# Power.net
KiCad netlist of a schematic drawn in Altium Designer
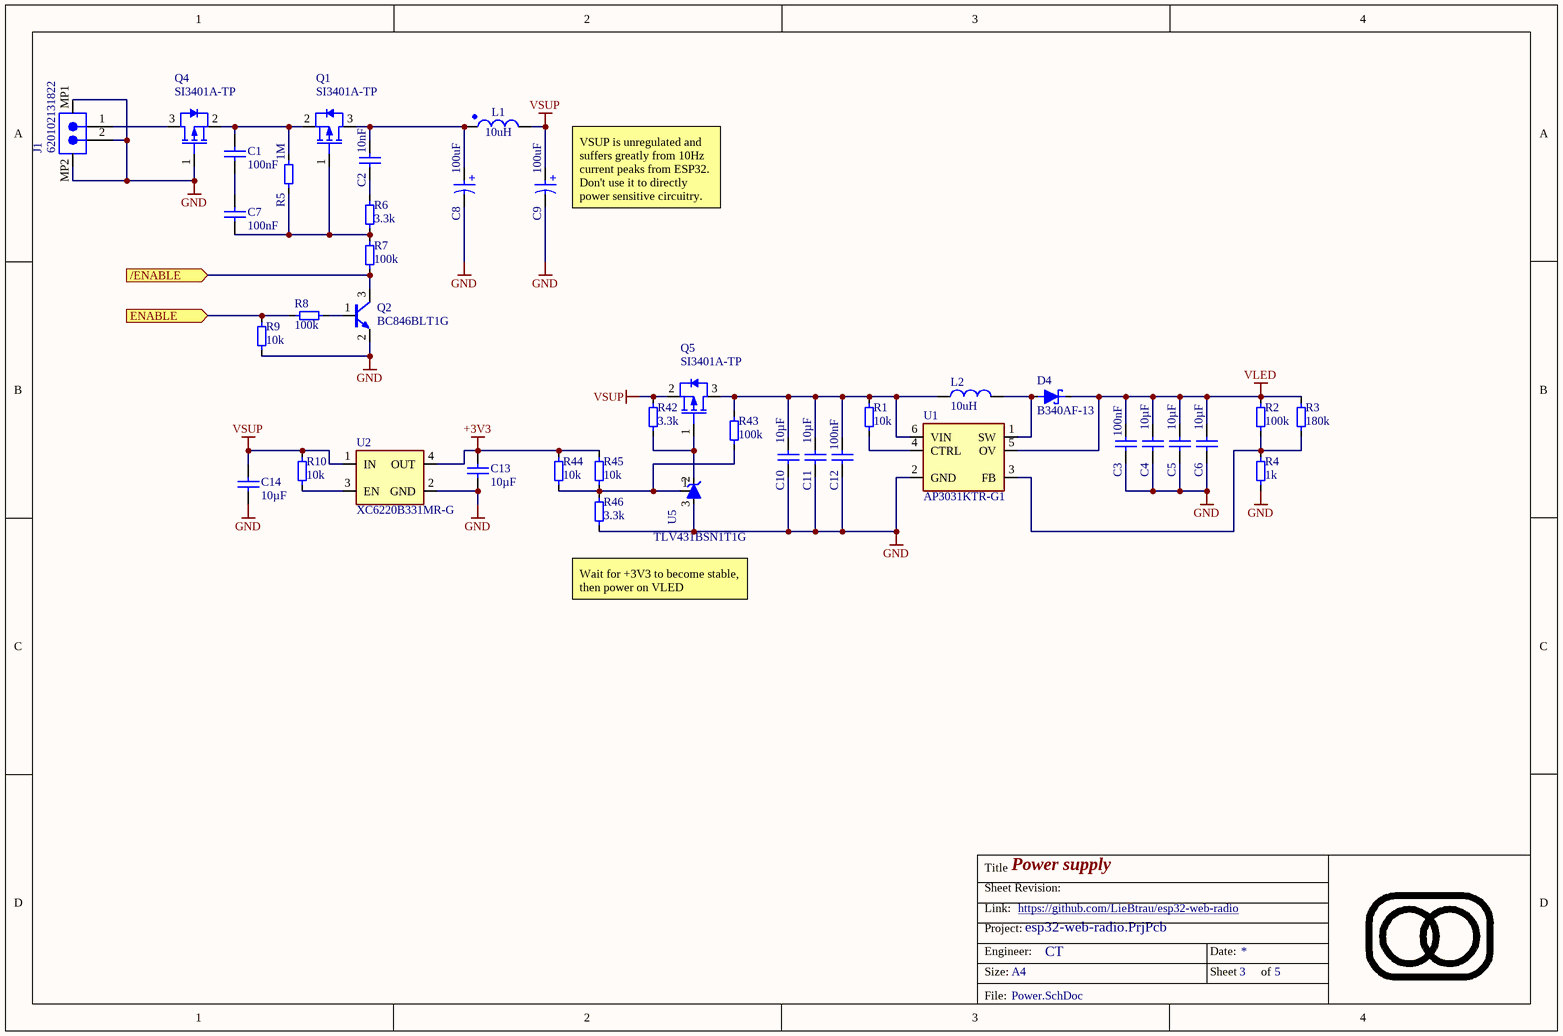
[diagram p0: Power.SchDoc]

(export (version "E")
  (design (tool "Eeschema 10.0.6"))
  (components
    (comp (ref "C1")
      (value "100nF")
      (footprint "0603-C-N")
      (description "WCAP-CSGP Multilayer Ceramic Chip Capacitor, General Purpose, size 0603, X7R, 100nF, 50VDC")
      (fields (field (name "TOLERANCE") "10%") (field (name "JLCPCB PART #") "C14663"))
      (libsource (lib "7c7 Engineering") (part "CAP-NP-2"))
    )
    (comp (ref "C2")
      (value "10nF")
      (footprint "0603-C-N")
      (description "Capacitor MLCC, General Purpose, size 0603, X7R, 10nF, +/-10%, 50V")
      (fields (field (name "TOLERANCE") "10%") (field (name "JLCPCB PART #") "C57112"))
      (libsource (lib "7c7 Engineering") (part "CAP-NP-2"))
    )
    (comp (ref "C3")
      (value "100nF")
      (footprint "0603-C-N")
      (description "WCAP-CSGP Multilayer Ceramic Chip Capacitor, General Purpose, size 0603, X7R, 100nF, 50VDC")
      (fields (field (name "TOLERANCE") "10%") (field (name "JLCPCB PART #") "C14663"))
      (libsource (lib "7c7 Engineering") (part "CAP-NP-2"))
    )
    (comp (ref "C4")
      (value "10µF")
      (footprint "WCAP-CSGP_1210_L3.2W2.5H2.5")
      (description "WCAP-CSGP Multilayer Ceramic Chip Capacitor, General Purpose, size 1210, X7R, 10µF, 50VDC")
      (fields (field (name "JLCPCB PART #") "C2918502") (field (name "TOLERANCE") "10%"))
      (libsource (lib "7c7 Engineering") (part "CAP-NP-2"))
    )
    (comp (ref "C5")
      (value "10µF")
      (footprint "WCAP-CSGP_1210_L3.2W2.5H2.5")
      (description "WCAP-CSGP Multilayer Ceramic Chip Capacitor, General Purpose, size 1210, X7R, 10µF, 50VDC")
      (fields (field (name "JLCPCB PART #") "C2918502") (field (name "TOLERANCE") "10%"))
      (libsource (lib "7c7 Engineering") (part "CAP-NP-2"))
    )
    (comp (ref "C6")
      (value "10µF")
      (footprint "WCAP-CSGP_1210_L3.2W2.5H2.5")
      (description "WCAP-CSGP Multilayer Ceramic Chip Capacitor, General Purpose, size 1210, X7R, 10µF, 50VDC")
      (fields (field (name "JLCPCB PART #") "C2918502") (field (name "TOLERANCE") "10%"))
      (libsource (lib "7c7 Engineering") (part "CAP-NP-2"))
    )
    (comp (ref "C7")
      (value "100nF")
      (footprint "0603-C-N")
      (description "WCAP-CSGP Multilayer Ceramic Chip Capacitor, General Purpose, size 0603, X7R, 100nF, 50VDC")
      (fields (field (name "TOLERANCE") "10%") (field (name "JLCPCB PART #") "C14663"))
      (libsource (lib "7c7 Engineering") (part "CAP-NP-2"))
    )
    (comp (ref "C8")
      (value "865080343009")
      (footprint "WCAP-ASLI_D6.3H5.5")
      (description "WCAP-ASLI Aluminum Electrolytic Capacitor, V-Chip, D6.3 x H5.5mm, 100uF, 16V")
      (fields
        (field (name "CAPACITANCE") "100uF")
        (field (name "MANUFACTURER") "Wurth Elektronik")
        (field (name "JLCPCB PART #") "C111600")
      )
      (libsource (lib "7c7 Engineering") (part "865081763011"))
    )
    (comp (ref "C9")
      (value "865080343009")
      (footprint "WCAP-ASLI_D6.3H5.5")
      (description "WCAP-ASLI Aluminum Electrolytic Capacitor, V-Chip, D6.3 x H5.5mm, 100uF, 16V")
      (fields
        (field (name "CAPACITANCE") "100uF")
        (field (name "MANUFACTURER") "Wurth Elektronik")
        (field (name "JLCPCB PART #") "C111600")
      )
      (libsource (lib "7c7 Engineering") (part "865081763011"))
    )
    (comp (ref "C10")
      (value "10µF")
      (footprint "1206-C-N")
      (description "WCAP-CSGP Multilayer Ceramic Chip Capacitor, General Purpose, size 1206, X7R, 10µF, 10VDC")
      (fields (field (name "TOLERANCE") "10%") (field (name "JLCPCB PART #") "C97953"))
      (libsource (lib "7c7 Engineering") (part "CAP-NP-2"))
    )
    (comp (ref "C11")
      (value "10µF")
      (footprint "1206-C-N")
      (description "WCAP-CSGP Multilayer Ceramic Chip Capacitor, General Purpose, size 1206, X7R, 10µF, 10VDC")
      (fields (field (name "TOLERANCE") "10%") (field (name "JLCPCB PART #") "C97953"))
      (libsource (lib "7c7 Engineering") (part "CAP-NP-2"))
    )
    (comp (ref "C12")
      (value "100nF")
      (footprint "0603-C-N")
      (description "WCAP-CSGP Multilayer Ceramic Chip Capacitor, General Purpose, size 0603, X7R, 100nF, 50VDC")
      (fields (field (name "TOLERANCE") "10%") (field (name "JLCPCB PART #") "C14663"))
      (libsource (lib "7c7 Engineering") (part "CAP-NP-2"))
    )
    (comp (ref "C13")
      (value "10µF")
      (footprint "1206-C-N")
      (description "WCAP-CSGP Multilayer Ceramic Chip Capacitor, General Purpose, size 1206, X7R, 10µF, 10VDC")
      (fields (field (name "TOLERANCE") "10%") (field (name "JLCPCB PART #") "C97953"))
      (libsource (lib "7c7 Engineering") (part "CAP-NP-2"))
    )
    (comp (ref "C14")
      (value "10µF")
      (footprint "1206-C-N")
      (description "WCAP-CSGP Multilayer Ceramic Chip Capacitor, General Purpose, size 1206, X7R, 10µF, 10VDC")
      (fields (field (name "TOLERANCE") "10%") (field (name "JLCPCB PART #") "C97953"))
      (libsource (lib "7c7 Engineering") (part "CAP-NP-2"))
    )
    (comp (ref "D4")
      (value "B340AF-13")
      (footprint "DO-214AC_UNI")
      (description "Diode 40 V 3A Surface Mount SMAF")
      (fields (field (name "JLCPCB PART #") "C5310924"))
      (libsource (lib "7c7 Engineering") (part "DIODE-SKY-2"))
    )
    (comp (ref "J1")
      (value "620102131822")
      (footprint "620102131822")
      (description "WR-WTB SMT Male Horizontal Shrouded Header, pitch 2mm, 2p")
      (fields (field (name "JLCPCB PART #") "C295747") (field (name "PUBLISHER") "Wurth Elektronik"))
      (libsource (lib "7c7 Engineering") (part "HDR_2P_2MP"))
    )
    (comp (ref "L1")
      (value "78438357100")
      (footprint "WE-MAIA_4030")
      (description "WE-MAIA SMT Power Inductor, size 4030, 10uH, 3.05A, 110mOhm")
      (fields
        (field (name "JLCPCB PART #") "C167879")
        (field (name "INDUCTANCE") "10uH")
        (field (name "MANUFACTURER") "Wurth Elektronik")
      )
      (libsource (lib "7c7 Engineering") (part "IND_POLAR-2"))
    )
    (comp (ref "L2")
      (value "10uH")
      (footprint "WE-PMI_1008_L2.5W2H1.2")
      (description "Inductor Power Chip Shielded Wirewound 10uH 20% 1MHz Metal 0.95A 0.48Ohm DCR 1008 T/R")
      (fields (field (name "TOLERANCE") "20%") (field (name "JLCPCB PART #") "C2042388"))
      (libsource (lib "7c7 Engineering") (part "IND"))
    )
    (comp (ref "Q1")
      (value "SI3401A-TP")
      (footprint "SOT-23-3-N")
      (description "Trans Mosfet P-ch 30V 4.2A 3-PIN SOT-23 T/r")
      (fields (field (name "JLCPCB PART #") "C15127"))
      (libsource (lib "7c7 Engineering") (part "PEMOS-GSD-3"))
    )
    (comp (ref "Q2")
      (value "BC846BLT1G")
      (footprint "SOT-23-3-N")
      (description "NPN Ic=100mA Vceo=65V hfe=200~450 P=225mW SOT-23")
      (fields (field (name "JLCPCB PART #") "C82477"))
      (libsource (lib "7c7 Engineering") (part "BJT-NPN-BEC"))
    )
    (comp (ref "Q4")
      (value "SI3401A-TP")
      (footprint "SOT-23-3-N")
      (description "Trans Mosfet P-ch 30V 4.2A 3-PIN SOT-23 T/r")
      (fields (field (name "JLCPCB PART #") "C15127"))
      (libsource (lib "7c7 Engineering") (part "PEMOS-GSD-3"))
    )
    (comp (ref "Q5")
      (value "SI3401A-TP")
      (footprint "SOT-23-3-N")
      (description "Trans Mosfet P-ch 30V 4.2A 3-PIN SOT-23 T/r")
      (fields (field (name "JLCPCB PART #") "C15127"))
      (libsource (lib "7c7 Engineering") (part "PEMOS-GSD-3"))
    )
    (comp (ref "R1")
      (value "10k")
      (footprint "0603-R-N")
      (description "Chip Resistor, Thick Film, General Purpose, 0603, 100mW, 50V, 10 kOhm, +/-1%")
      (fields (field (name "JLCPCB PART #") "C25804") (field (name "TOLERANCE") "1%"))
      (libsource (lib "") (part "RES_2"))
    )
    (comp (ref "R2")
      (value "100k")
      (footprint "0603-R-N")
      (description "Chip Resistor, Thick Film, General Purpose, 0603, 100mW, 50V, 100 kOhm, +/-1%")
      (fields (field (name "TOLERANCE") "1%") (field (name "JLCPCB PART #") "C25803"))
      (libsource (lib "") (part "RES_1"))
    )
    (comp (ref "R3")
      (value "180k")
      (footprint "0603-R-N")
      (description "Res Thick Film 0603 180K Ohm 1% 0.1W(1/10W) ±100ppm/C Pad SMD T/R")
      (fields (field (name "TOLERANCE") "1%") (field (name "JLCPCB PART #") "C22827"))
      (libsource (lib "") (part "RES_2"))
    )
    (comp (ref "R4")
      (value "1k")
      (footprint "0603-R-N")
      (description "Chip Resistor, Thick Film, General Purpose, 0603, 100mW, 50V, 1 kOhm, +/-1%")
      (fields (field (name "TOLERANCE") "1%") (field (name "JLCPCB PART #") "C21190"))
      (libsource (lib "") (part "RES_1"))
    )
    (comp (ref "R5")
      (value "1M")
      (footprint "0603-R-N")
      (description "Chip Resistor, Thick Film, General Purpose, 0603, 100mW, 50V, 1 MOhm, +/-1%")
      (fields (field (name "TOLERANCE") "1%") (field (name "JLCPCB PART #") "C22935"))
      (libsource (lib "") (part "RES_2"))
    )
    (comp (ref "R6")
      (value "3.3k")
      (footprint "0603-R-N")
      (description "Chip Resistor, Thick Film, General Purpose, 0603, 100mW, 50V, 3.3 kOhm, +/-1%")
      (fields (field (name "TOLERANCE") "1%") (field (name "JLCPCB PART #") "C22978"))
      (libsource (lib "") (part "RES_1"))
    )
    (comp (ref "R7")
      (value "100k")
      (footprint "0603-R-N")
      (description "Chip Resistor, Thick Film, General Purpose, 0603, 100mW, 50V, 100 kOhm, +/-1%")
      (fields (field (name "TOLERANCE") "1%") (field (name "JLCPCB PART #") "C25803"))
      (libsource (lib "") (part "RES_1"))
    )
    (comp (ref "R8")
      (value "100k")
      (footprint "0603-R-N")
      (description "Chip Resistor, Thick Film, General Purpose, 0603, 100mW, 50V, 100 kOhm, +/-1%")
      (fields (field (name "TOLERANCE") "1%") (field (name "JLCPCB PART #") "C25803"))
      (libsource (lib "") (part "RES_2"))
    )
    (comp (ref "R9")
      (value "10k")
      (footprint "0603-R-N")
      (description "Chip Resistor, Thick Film, General Purpose, 0603, 100mW, 50V, 10 kOhm, +/-1%")
      (fields (field (name "JLCPCB PART #") "C25804") (field (name "TOLERANCE") "1%"))
      (libsource (lib "7c7 Engineering") (part "RES"))
    )
    (comp (ref "R10")
      (value "10k")
      (footprint "0603-R-N")
      (description "Chip Resistor, Thick Film, General Purpose, 0603, 100mW, 50V, 10 kOhm, +/-1%")
      (fields (field (name "JLCPCB PART #") "C25804") (field (name "TOLERANCE") "1%"))
      (libsource (lib "") (part "RES_2"))
    )
    (comp (ref "R42")
      (value "3.3k")
      (footprint "0603-R-N")
      (description "Chip Resistor, Thick Film, General Purpose, 0603, 100mW, 50V, 3.3 kOhm, +/-1%")
      (fields (field (name "TOLERANCE") "1%") (field (name "JLCPCB PART #") "C22978"))
      (libsource (lib "") (part "RES_1"))
    )
    (comp (ref "R43")
      (value "100k")
      (footprint "0603-R-N")
      (description "Chip Resistor, Thick Film, General Purpose, 0603, 100mW, 50V, 100 kOhm, +/-1%")
      (fields (field (name "TOLERANCE") "1%") (field (name "JLCPCB PART #") "C25803"))
      (libsource (lib "7c7 Engineering") (part "RES"))
    )
    (comp (ref "R44")
      (value "10k")
      (footprint "0603-R-N")
      (description "Chip Resistor, Thick Film, General Purpose, 0603, 100mW, 50V, 10 kOhm, +/-1%")
      (fields (field (name "JLCPCB PART #") "C25804") (field (name "TOLERANCE") "1%"))
      (libsource (lib "7c7 Engineering") (part "RES"))
    )
    (comp (ref "R45")
      (value "10k")
      (footprint "0603-R-N")
      (description "Chip Resistor, Thick Film, General Purpose, 0603, 100mW, 50V, 10 kOhm, +/-1%")
      (fields (field (name "JLCPCB PART #") "C25804") (field (name "TOLERANCE") "1%"))
      (libsource (lib "7c7 Engineering") (part "RES"))
    )
    (comp (ref "R46")
      (value "3.3k")
      (footprint "0603-R-N")
      (description "Chip Resistor, Thick Film, General Purpose, 0603, 100mW, 50V, 3.3 kOhm, +/-1%")
      (fields (field (name "TOLERANCE") "1%") (field (name "JLCPCB PART #") "C22978"))
      (libsource (lib "") (part "RES_1"))
    )
    (comp (ref "U1")
      (value "AP3031KTR-G1")
      (footprint "SOT-23-6")
      (description "AP3031 Series 2.7 to 16 Vin 1.4 A White LED Step Up Converter-SOT-23-6")
      (fields (field (name "JLCPCB PART #") "C82636"))
      (libsource (lib "7c7 Engineering") (part "AP3031KTR-G1-Symbol-1"))
    )
    (comp (ref "U2")
      (value "XC6220B331MR-G")
      (footprint "SOT25-N")
      (description "Fixed LDO 3.3V, 1%, 1A, Iq 108uA, -40°C to 85°C")
      (fields (field (name "JLCPCB PART #") "C86534"))
      (libsource (lib "7c7 Engineering") (part "LDO-with-enable"))
    )
    (comp (ref "U5")
      (value "TLV431BSN1T1G")
      (footprint "SOT-23-3-N")
      (description "Adjustable Shunt Voltage Reference 1.24 - 16V; +/-0.5%; 3-Pin SOT-23")
      (fields (field (name "TOLERANCE") "0.5%") (field (name "JLCPCB PART #") "C91075"))
      (libsource (lib "7c7 Engineering") (part "TLV431BSN1T1G"))
    )
  )
  (nets
    (net (code "1") (name "+3V3") (class "Default")
      (node (ref "C13") (pin "2") (pinfunction "2_2") (pintype "passive"))
      (node (ref "R44") (pin "2") (pinfunction "2_2") (pintype "passive"))
      (node (ref "R45") (pin "2") (pinfunction "2_2") (pintype "passive"))
      (node (ref "U2") (pin "4") (pinfunction "OUT_4") (pintype "power_in"))
    )
    (net (code "2") (name "/ENABLE") (class "Default")
      (node (ref "R8") (pin "1") (pinfunction "1_1") (pintype "passive"))
      (node (ref "R9") (pin "2") (pinfunction "2_2") (pintype "passive"))
    )
    (net (code "3") (name "/{slash}ENABLE") (class "Default")
      (node (ref "Q2") (pin "3") (pinfunction "C_3") (pintype "passive"))
      (node (ref "R7") (pin "2") (pinfunction "2_2") (pintype "passive"))
    )
    (net (code "4") (name "GND") (class "Default")
      (node (ref "C10") (pin "1") (pinfunction "1_1") (pintype "passive"))
      (node (ref "C11") (pin "1") (pinfunction "1_1") (pintype "passive"))
      (node (ref "C12") (pin "1") (pinfunction "1_1") (pintype "passive"))
      (node (ref "C13") (pin "1") (pinfunction "1_1") (pintype "passive"))
      (node (ref "C14") (pin "1") (pinfunction "1_1") (pintype "passive"))
      (node (ref "C3") (pin "1") (pinfunction "1_1") (pintype "passive"))
      (node (ref "C4") (pin "1") (pinfunction "1_1") (pintype "passive"))
      (node (ref "C5") (pin "1") (pinfunction "1_1") (pintype "passive"))
      (node (ref "C6") (pin "1") (pinfunction "1_1") (pintype "passive"))
      (node (ref "C8") (pin "2") (pinfunction "N_2") (pintype "passive"))
      (node (ref "C9") (pin "2") (pinfunction "N_2") (pintype "passive"))
      (node (ref "J1") (pin "2") (pinfunction "2_2") (pintype "passive"))
      (node (ref "J1") (pin "MP1") (pinfunction "MP1_MP1") (pintype "passive"))
      (node (ref "J1") (pin "MP2") (pinfunction "MP2_MP2") (pintype "passive"))
      (node (ref "Q2") (pin "2") (pinfunction "E_2") (pintype "passive"))
      (node (ref "Q4") (pin "1") (pinfunction "GATE_1") (pintype "passive"))
      (node (ref "R4") (pin "2") (pinfunction "2_2") (pintype "passive"))
      (node (ref "R46") (pin "2") (pinfunction "2_2") (pintype "passive"))
      (node (ref "R9") (pin "1") (pinfunction "1_1") (pintype "passive"))
      (node (ref "U1") (pin "2") (pinfunction "GND_2") (pintype "power_in"))
      (node (ref "U2") (pin "2") (pinfunction "GND_2") (pintype "power_in"))
      (node (ref "U5") (pin "3") (pinfunction "A_3") (pintype "power_in"))
    )
    (net (code "5") (name "Net-(C1-Pad1)") (class "Default")
      (node (ref "C1") (pin "1") (pinfunction "1_1") (pintype "passive"))
      (node (ref "C7") (pin "1") (pinfunction "1_1") (pintype "passive"))
    )
    (net (code "6") (name "Net-(C2-Pad1)") (class "Default")
      (node (ref "C2") (pin "1") (pinfunction "1_1") (pintype "passive"))
      (node (ref "R6") (pin "1") (pinfunction "1_1") (pintype "passive"))
    )
    (net (code "7") (name "Net-(C8-P)") (class "Default")
      (node (ref "C2") (pin "2") (pinfunction "2_2") (pintype "passive"))
      (node (ref "C8") (pin "1") (pinfunction "P_1") (pintype "passive"))
      (node (ref "L1") (pin "1") (pinfunction "1_1") (pintype "passive"))
      (node (ref "Q1") (pin "3") (pinfunction "DRAIN_3") (pintype "passive"))
    )
    (net (code "8") (name "Net-(D4-A)") (class "Default")
      (node (ref "D4") (pin "2") (pinfunction "A_2") (pintype "passive"))
      (node (ref "L2") (pin "2") (pinfunction "2_2") (pintype "passive"))
      (node (ref "U1") (pin "1") (pinfunction "SW_1") (pintype "power_in"))
    )
    (net (code "9") (name "Net-(Q1-GATE)") (class "Default")
      (node (ref "C7") (pin "2") (pinfunction "2_2") (pintype "passive"))
      (node (ref "Q1") (pin "1") (pinfunction "GATE_1") (pintype "passive"))
      (node (ref "R5") (pin "1") (pinfunction "1_1") (pintype "passive"))
      (node (ref "R6") (pin "2") (pinfunction "2_2") (pintype "passive"))
      (node (ref "R7") (pin "1") (pinfunction "1_1") (pintype "passive"))
    )
    (net (code "10") (name "Net-(Q1-SOURCE)") (class "Default")
      (node (ref "C1") (pin "2") (pinfunction "2_2") (pintype "passive"))
      (node (ref "Q1") (pin "2") (pinfunction "SOURCE_2") (pintype "passive"))
      (node (ref "Q4") (pin "2") (pinfunction "SOURCE_2") (pintype "passive"))
      (node (ref "R5") (pin "2") (pinfunction "2_2") (pintype "passive"))
    )
    (net (code "11") (name "Net-(Q2-B)") (class "Default")
      (node (ref "Q2") (pin "1") (pinfunction "B_1") (pintype "passive"))
      (node (ref "R8") (pin "2") (pinfunction "2_2") (pintype "passive"))
    )
    (net (code "12") (name "Net-(Q4-DRAIN)") (class "Default")
      (node (ref "J1") (pin "1") (pinfunction "1_1") (pintype "passive"))
      (node (ref "Q4") (pin "3") (pinfunction "DRAIN_3") (pintype "passive"))
    )
    (net (code "13") (name "Net-(Q5-DRAIN)") (class "Default")
      (node (ref "C10") (pin "2") (pinfunction "2_2") (pintype "passive"))
      (node (ref "C11") (pin "2") (pinfunction "2_2") (pintype "passive"))
      (node (ref "C12") (pin "2") (pinfunction "2_2") (pintype "passive"))
      (node (ref "L2") (pin "1") (pinfunction "1_1") (pintype "passive"))
      (node (ref "Q5") (pin "3") (pinfunction "DRAIN_3") (pintype "passive"))
      (node (ref "R1") (pin "2") (pinfunction "2_2") (pintype "passive"))
      (node (ref "R43") (pin "2") (pinfunction "2_2") (pintype "passive"))
      (node (ref "U1") (pin "6") (pinfunction "VIN_6") (pintype "power_in"))
    )
    (net (code "14") (name "Net-(Q5-GATE)") (class "Default")
      (node (ref "Q5") (pin "1") (pinfunction "GATE_1") (pintype "passive"))
      (node (ref "R42") (pin "2") (pinfunction "2_2") (pintype "passive"))
      (node (ref "U5") (pin "2") (pinfunction "C_2") (pintype "power_in"))
    )
    (net (code "15") (name "Net-(U1-CTRL)") (class "Default")
      (node (ref "R1") (pin "1") (pinfunction "1_1") (pintype "passive"))
      (node (ref "U1") (pin "4") (pinfunction "CTRL_4") (pintype "power_in"))
    )
    (net (code "16") (name "Net-(U1-FB)") (class "Default")
      (node (ref "R2") (pin "2") (pinfunction "2_2") (pintype "passive"))
      (node (ref "R3") (pin "1") (pinfunction "1_1") (pintype "passive"))
      (node (ref "R4") (pin "1") (pinfunction "1_1") (pintype "passive"))
      (node (ref "U1") (pin "3") (pinfunction "FB_3") (pintype "power_in"))
    )
    (net (code "17") (name "Net-(U2-EN)") (class "Default")
      (node (ref "R10") (pin "1") (pinfunction "1_1") (pintype "passive"))
      (node (ref "U2") (pin "3") (pinfunction "EN_3") (pintype "passive"))
    )
    (net (code "18") (name "Net-(U5-rEF)") (class "Default")
      (node (ref "R43") (pin "1") (pinfunction "1_1") (pintype "passive"))
      (node (ref "R44") (pin "1") (pinfunction "1_1") (pintype "passive"))
      (node (ref "R45") (pin "1") (pinfunction "1_1") (pintype "passive"))
      (node (ref "R46") (pin "1") (pinfunction "1_1") (pintype "passive"))
      (node (ref "U5") (pin "1") (pinfunction "rEF_1") (pintype "passive"))
    )
    (net (code "19") (name "VLED") (class "Default")
      (node (ref "C3") (pin "2") (pinfunction "2_2") (pintype "passive"))
      (node (ref "C4") (pin "2") (pinfunction "2_2") (pintype "passive"))
      (node (ref "C5") (pin "2") (pinfunction "2_2") (pintype "passive"))
      (node (ref "C6") (pin "2") (pinfunction "2_2") (pintype "passive"))
      (node (ref "D4") (pin "1") (pinfunction "K_1") (pintype "passive"))
      (node (ref "R2") (pin "1") (pinfunction "1_1") (pintype "passive"))
      (node (ref "R3") (pin "2") (pinfunction "2_2") (pintype "passive"))
      (node (ref "U1") (pin "5") (pinfunction "OV_5") (pintype "power_in"))
    )
    (net (code "20") (name "VSUP") (class "Default")
      (node (ref "C14") (pin "2") (pinfunction "2_2") (pintype "passive"))
      (node (ref "C9") (pin "1") (pinfunction "P_1") (pintype "passive"))
      (node (ref "L1") (pin "2") (pinfunction "2_2") (pintype "passive"))
      (node (ref "Q5") (pin "2") (pinfunction "SOURCE_2") (pintype "passive"))
      (node (ref "R10") (pin "2") (pinfunction "2_2") (pintype "passive"))
      (node (ref "R42") (pin "1") (pinfunction "1_1") (pintype "passive"))
      (node (ref "U2") (pin "1") (pinfunction "IN_1") (pintype "power_in"))
    )
  )
)
